# CH32F203CBT6-R1.net
KiCad netlist of a schematic drawn in Altium Designer
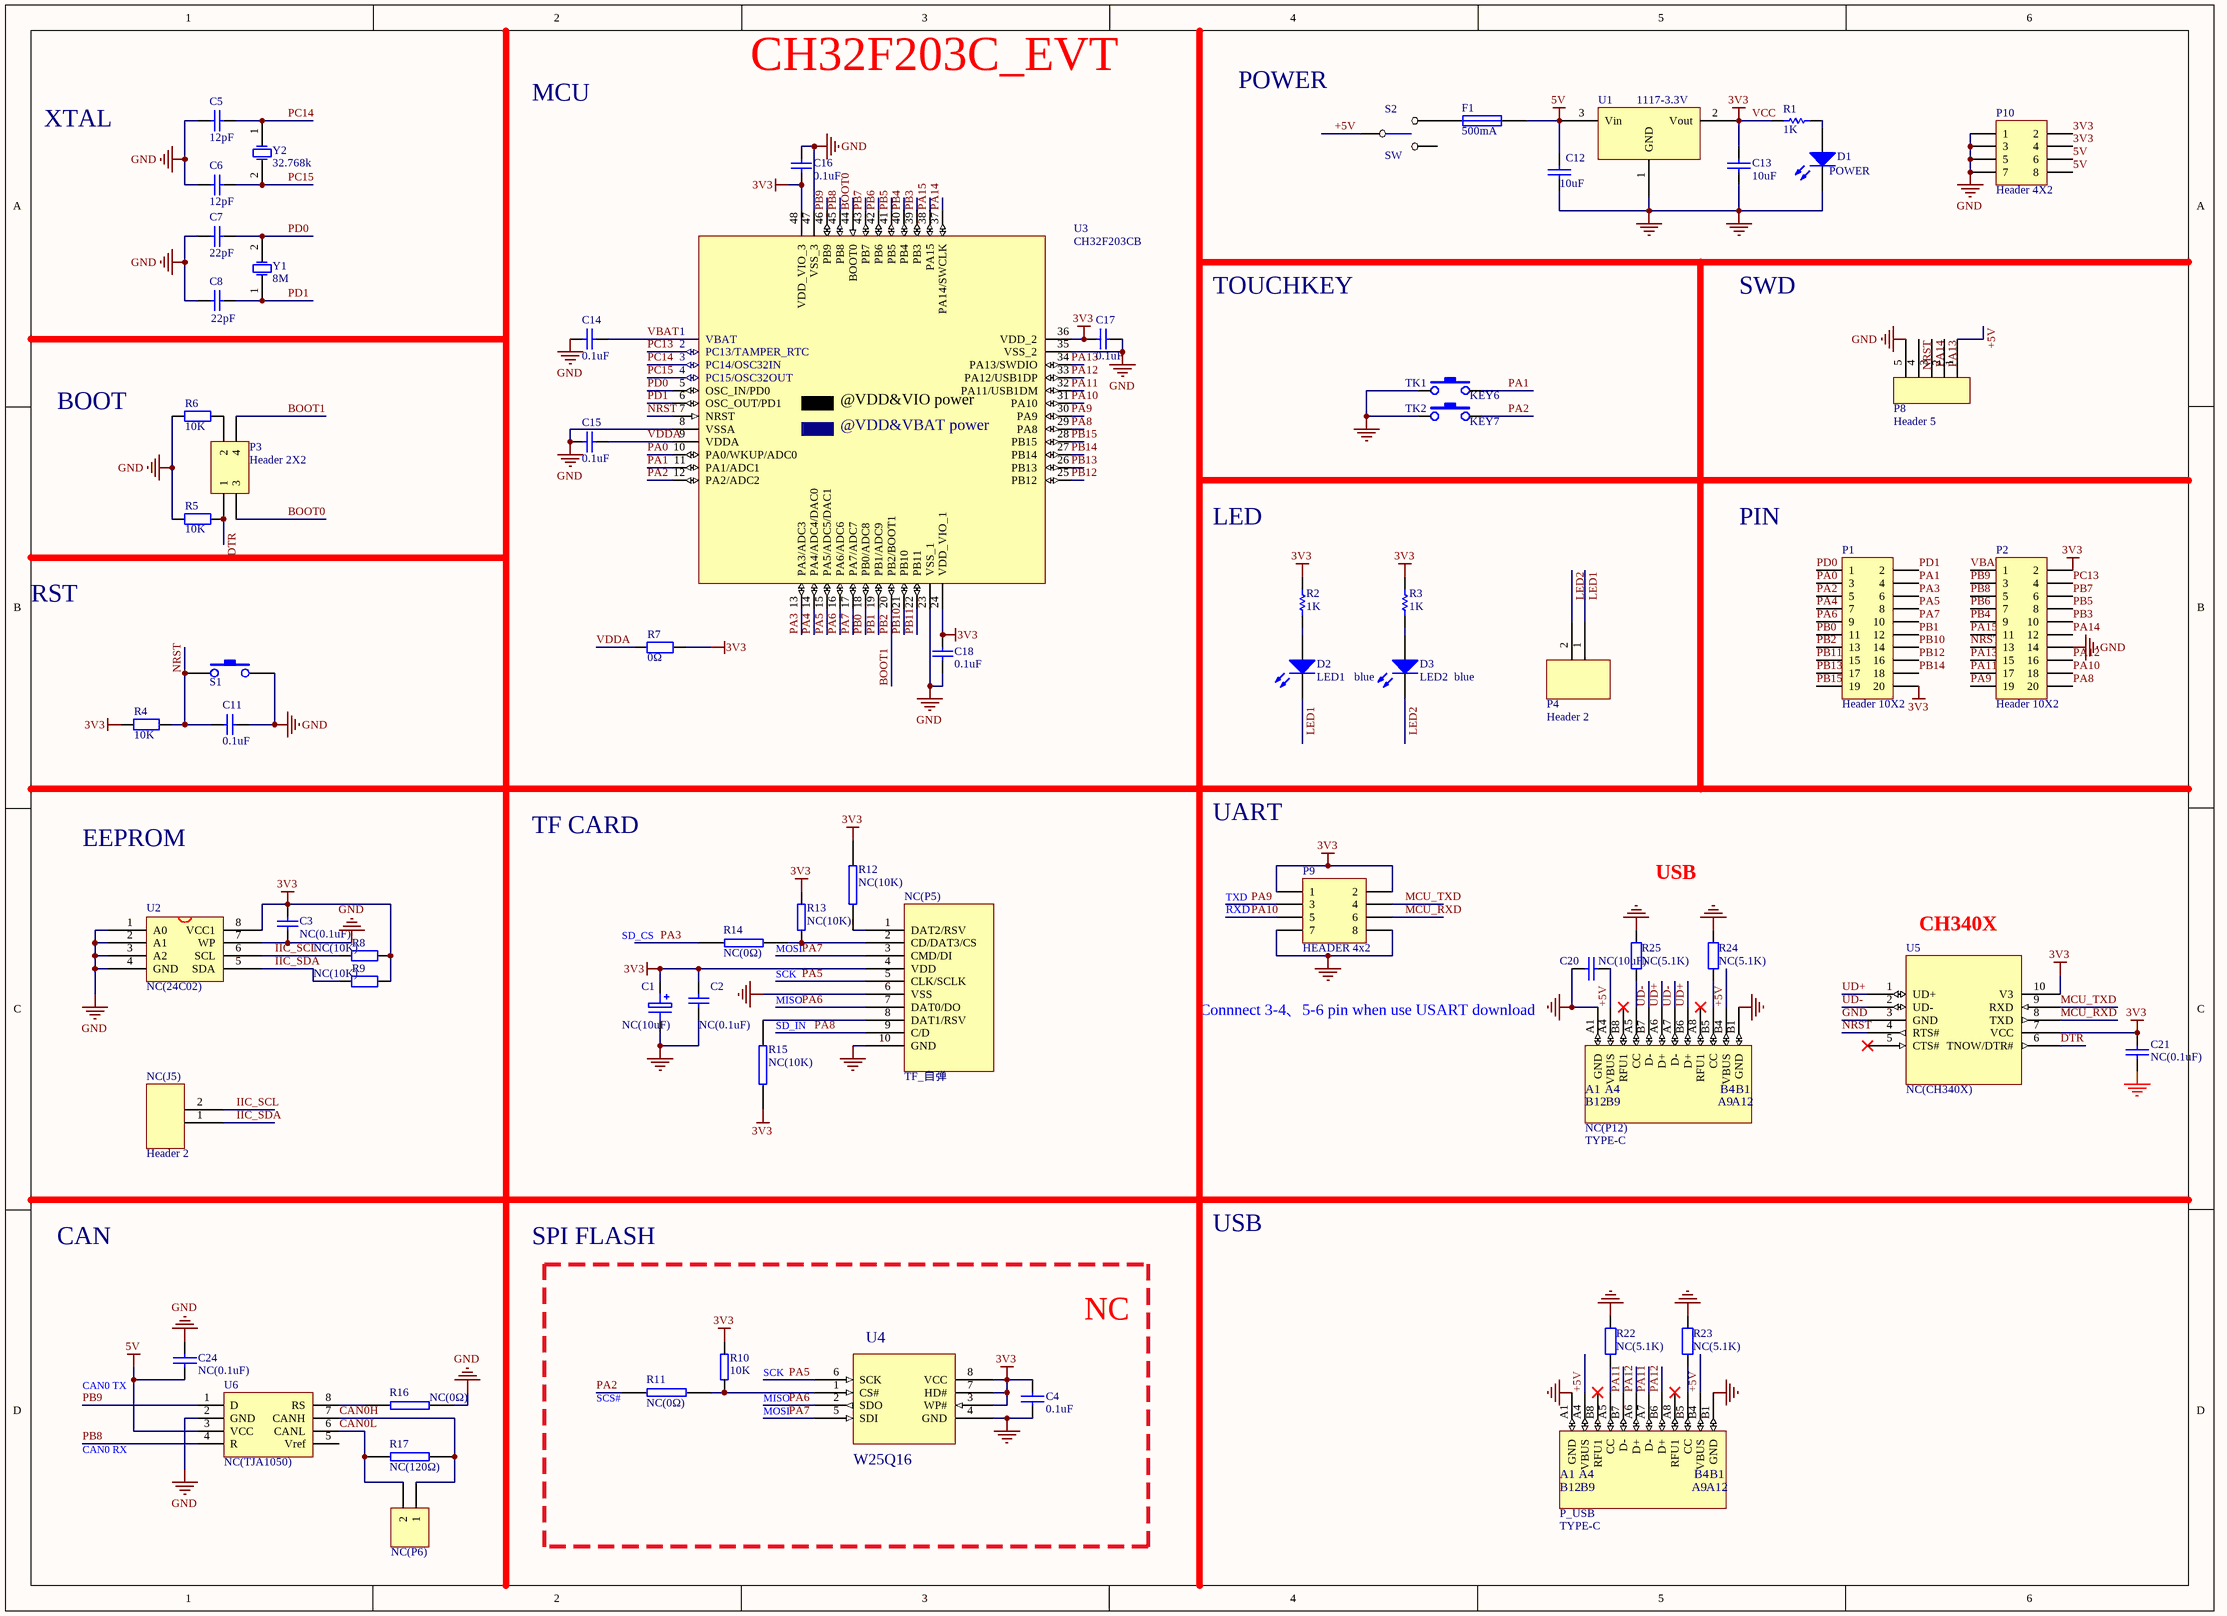
[diagram p0: CH32F203CBT6-R1.SchDoc]

(export (version "E")
  (design (tool "Eeschema 10.0.6"))
  (components
    (comp (ref "C1")
      (value "NC(10uF)")
      (footprint "3216")
      (description "Electrolytic Capacitor")
      (libsource (lib "*") (part "ELECTRO1"))
    )
    (comp (ref "C2")
      (value "NC(0.1uF)")
      (footprint "0603")
      (description "Capacitor")
      (fields (field (name "Comment") "0.1uF") (field (name "PUBLISHER") "Altium Limited"))
      (libsource (lib "*") (part "Cap"))
    )
    (comp (ref "C3")
      (value "NC(0.1uF)")
      (footprint "0603")
      (description "Capacitor")
      (fields (field (name "PUBLISHER") "Altium Limited"))
      (libsource (lib "Miscellaneous Devices") (part "Cap"))
    )
    (comp (ref "C4")
      (value "0.1uF")
      (footprint "0603")
      (description "Capacitor")
      (libsource (lib "") (part "CAP_1"))
    )
    (comp (ref "C5")
      (value "12pF")
      (footprint "0603")
      (description "Capacitor")
      (fields (field (name "PUBLISHER") "Altium Limited"))
      (libsource (lib "Miscellaneous Devices") (part "Cap"))
    )
    (comp (ref "C6")
      (value "12pF")
      (footprint "0603")
      (description "Capacitor")
      (fields (field (name "PUBLISHER") "Altium Limited"))
      (libsource (lib "Miscellaneous Devices") (part "Cap"))
    )
    (comp (ref "C7")
      (value "22pF")
      (footprint "0603")
      (description "Capacitor")
      (fields (field (name "PUBLISHER") "Altium Limited"))
      (libsource (lib "Miscellaneous Devices") (part "Cap"))
    )
    (comp (ref "C8")
      (value "22pF")
      (footprint "0603")
      (description "Capacitor")
      (fields (field (name "PUBLISHER") "Altium Limited"))
      (libsource (lib "Miscellaneous Devices") (part "Cap"))
    )
    (comp (ref "C11")
      (value "0.1uF")
      (footprint "0603")
      (description "Capacitor")
      (fields (field (name "PUBLISHER") "Altium Limited"))
      (libsource (lib "Miscellaneous Devices") (part "Cap"))
    )
    (comp (ref "C12")
      (value "10uF")
      (footprint "3216")
      (description "Capacitor")
      (libsource (lib "*") (part "CAP"))
    )
    (comp (ref "C13")
      (value "10uF")
      (footprint "0603")
      (description "Capacitor")
      (libsource (lib "*") (part "CAP"))
    )
    (comp (ref "C14")
      (value "0.1uF")
      (footprint "0603")
      (description "Capacitor")
      (fields (field (name "PUBLISHER") "Altium Limited"))
      (libsource (lib "Miscellaneous Devices") (part "Cap"))
    )
    (comp (ref "C15")
      (value "0.1uF")
      (footprint "0603")
      (description "Capacitor")
      (fields (field (name "PUBLISHER") "Altium Limited"))
      (libsource (lib "Miscellaneous Devices") (part "Cap"))
    )
    (comp (ref "C16")
      (value "0.1uF")
      (footprint "0603")
      (description "Capacitor")
      (fields (field (name "PUBLISHER") "Altium Limited"))
      (libsource (lib "Miscellaneous Devices") (part "Cap"))
    )
    (comp (ref "C17")
      (value "0.1uF")
      (footprint "0603")
      (description "Capacitor")
      (fields (field (name "PUBLISHER") "Altium Limited"))
      (libsource (lib "Miscellaneous Devices") (part "Cap"))
    )
    (comp (ref "C18")
      (value "0.1uF")
      (footprint "0603")
      (description "Capacitor")
      (fields (field (name "PUBLISHER") "Altium Limited"))
      (libsource (lib "Miscellaneous Devices") (part "Cap"))
    )
    (comp (ref "C20")
      (value "NC(10uF)")
      (footprint "3216_C")
      (description "Capacitor")
      (libsource (lib "*") (part "CAP"))
    )
    (comp (ref "C21")
      (value "NC(0.1uF)")
      (footprint "0603_C")
      (description "Capacitor")
      (libsource (lib "*") (part "CAP"))
    )
    (comp (ref "C24")
      (value "NC(0.1uF)")
      (footprint "0603")
      (description "Capacitor")
      (libsource (lib "") (part "CAP_1"))
    )
    (comp (ref "D1")
      (value "POWER")
      (footprint "0603L")
      (description "Typical INFRARED GaAs LED")
      (fields (field (name "PUBLISHER") "Altium Limited"))
      (libsource (lib "Miscellaneous Devices") (part "LED0"))
    )
    (comp (ref "D2")
      (value "LED1   blue")
      (footprint "0603L")
      (description "Typical INFRARED GaAs LED")
      (fields (field (name "PUBLISHER") "Altium Limited"))
      (libsource (lib "Miscellaneous Devices") (part "LED0"))
    )
    (comp (ref "D3")
      (value "LED2  blue")
      (footprint "0603L")
      (description "Typical INFRARED GaAs LED")
      (fields (field (name "PUBLISHER") "Altium Limited"))
      (libsource (lib "Miscellaneous Devices") (part "LED0"))
    )
    (comp (ref "F1")
      (value "500mA")
      (footprint "0603")
      (description "Fuse")
      (libsource (lib "*") (part "FUSE1"))
    )
    (comp (ref "NC(J5)")
      (value "Header 2")
      (footprint "SIP2 - 40mil")
      (libsource (lib "MYSCH") (part "2HEAD"))
    )
    (comp (ref "NC(P5)") (value "TF_自弹") (footprint "TF_CARD") (libsource (lib "*") (part "TF_自弹")))
    (comp (ref "NC(P6)")
      (value "Header 2")
      (footprint "PORT2 4.5MM")
      (description "Header, 2-Pin")
      (fields (field (name "PUBLISHER") "Altium Limited"))
      (libsource (lib "Miscellaneous Connectors") (part "Header 2"))
    )
    (comp (ref "NC(P12)")
      (value "TYPE-C")
      (footprint "TYPE-C-Receptacle-2.0")
      (libsource (lib "*") (part "TYPE-C1"))
    )
    (comp (ref "P1")
      (value "Header 10X2")
      (footprint "IDC20")
      (description "Header, 10-Pin, Dual row")
      (fields (field (name "PUBLISHER") "Altium Limited"))
      (libsource (lib "Miscellaneous Connectors") (part "Header 10X2"))
    )
    (comp (ref "P2")
      (value "Header 10X2")
      (footprint "IDC20")
      (description "Header, 10-Pin, Dual row")
      (fields (field (name "PUBLISHER") "Altium Limited"))
      (libsource (lib "Miscellaneous Connectors") (part "Header 10X2"))
    )
    (comp (ref "P3")
      (value "Header 2X2")
      (footprint "HDR2X2")
      (description "Header, 2-Pin, Dual row")
      (fields (field (name "PUBLISHER") "Altium Limited"))
      (libsource (lib "Miscellaneous Connectors") (part "Header 2X2"))
    )
    (comp (ref "P4") (value "Header 2") (footprint "SIP2 - 40mil") (libsource (lib "") (part "2HEAD_1")))
    (comp (ref "P8")
      (value "Header 5")
      (footprint "SIP5 - 40mil")
      (libsource (lib "PCB_Project1") (part "2HEAD"))
    )
    (comp (ref "P9")
      (value "HEADER 4x2")
      (footprint "MYPCB:IDC8-2.54mm")
      (description "Header, 4-Pin, Dual row")
      (libsource (lib "wch_sch_others") (part "HEADER 4x2"))
    )
    (comp (ref "P10")
      (value "Header 4X2")
      (footprint "IDC8")
      (description "Header, 4-Pin, Dual row")
      (fields (field (name "PUBLISHER") "Altium Limited"))
      (libsource (lib "Miscellaneous Connectors") (part "Header 4X2"))
    )
    (comp (ref "P_USB")
      (value "TYPE-C")
      (footprint "TYPE-C-Receptacle-2.0")
      (libsource (lib "*") (part "TYPE-C1"))
    )
    (comp (ref "R1")
      (value "1K")
      (footprint "0603")
      (description "Semiconductor Resistor")
      (fields (field (name "PUBLISHER") "Altium Limited"))
      (libsource (lib "Miscellaneous Devices") (part "Res Semi"))
    )
    (comp (ref "R2")
      (value "1K")
      (footprint "0603")
      (description "Semiconductor Resistor")
      (fields (field (name "PUBLISHER") "Altium Limited"))
      (libsource (lib "Miscellaneous Devices") (part "Res Semi"))
    )
    (comp (ref "R3")
      (value "1K")
      (footprint "0603")
      (description "Semiconductor Resistor")
      (fields (field (name "PUBLISHER") "Altium Limited"))
      (libsource (lib "Miscellaneous Devices") (part "Res Semi"))
    )
    (comp (ref "R4")
      (value "10K")
      (footprint "0603")
      (description "Resistor")
      (fields (field (name "PUBLISHER") "Altium Limited"))
      (libsource (lib "") (part "Res2_1"))
    )
    (comp (ref "R5")
      (value "10K")
      (footprint "0603")
      (description "Resistor")
      (fields (field (name "PUBLISHER") "Altium Limited"))
      (libsource (lib "") (part "Res2_1"))
    )
    (comp (ref "R6")
      (value "10K")
      (footprint "0603")
      (description "Resistor")
      (fields (field (name "PUBLISHER") "Altium Limited"))
      (libsource (lib "") (part "Res2_1"))
    )
    (comp (ref "R7")
      (value "0Ω")
      (footprint "0603")
      (description "Resistor")
      (fields (field (name "PUBLISHER") "Altium Limited"))
      (libsource (lib "") (part "Res2_1"))
    )
    (comp (ref "R8")
      (value "NC(10K)")
      (footprint "0603")
      (description "Resistor")
      (fields (field (name "PUBLISHER") "Altium Limited"))
      (libsource (lib "") (part "Res2_1"))
    )
    (comp (ref "R9")
      (value "NC(10K)")
      (footprint "0603")
      (description "Resistor")
      (fields (field (name "PUBLISHER") "Altium Limited"))
      (libsource (lib "") (part "Res2_1"))
    )
    (comp (ref "R10") (value "10K") (footprint "0603") (libsource (lib "*") (part "DZ")))
    (comp (ref "R11") (value "NC(0Ω)") (footprint "0603") (libsource (lib "*") (part "RES2")))
    (comp (ref "R12") (value "NC(10K)") (footprint "0603") (libsource (lib "*") (part "RES2")))
    (comp (ref "R13") (value "NC(10K)") (footprint "0603") (libsource (lib "*") (part "DZ")))
    (comp (ref "R14") (value "NC(0Ω)") (footprint "0603") (libsource (lib "*") (part "RES2")))
    (comp (ref "R15") (value "NC(10K)") (footprint "0603") (libsource (lib "*") (part "RES2")))
    (comp (ref "R16") (value "NC(0Ω)") (footprint "0603") (libsource (lib "*") (part "RES2")))
    (comp (ref "R17") (value "NC(120Ω)") (footprint "0603") (libsource (lib "*") (part "RES2")))
    (comp (ref "R22")
      (value "NC(5.1K)")
      (footprint "0603")
      (description "Resistor")
      (libsource (lib "Miscellaneous Devices") (part "Res2"))
    )
    (comp (ref "R23")
      (value "NC(5.1K)")
      (footprint "0603")
      (description "Resistor")
      (libsource (lib "Miscellaneous Devices") (part "Res2"))
    )
    (comp (ref "R24")
      (value "NC(5.1K)")
      (footprint "0603")
      (description "Resistor")
      (libsource (lib "Miscellaneous Devices") (part "Res2"))
    )
    (comp (ref "R25")
      (value "NC(5.1K)")
      (footprint "0603")
      (description "Resistor")
      (libsource (lib "Miscellaneous Devices") (part "Res2"))
    )
    (comp (ref "S1") (value "KEY") (footprint "贴片按键") (libsource (lib "CCDXPLIB") (part "KEY")))
    (comp (ref "S2") (value "SW") (footprint "KEY2") (libsource (lib "MYSCH") (part "SW")))
    (comp (ref "TK1") (value "KEY6") (footprint "KEY68") (libsource (lib "*") (part "KEY")))
    (comp (ref "TK2") (value "KEY7") (footprint "KEY68") (libsource (lib "*") (part "KEY")))
    (comp (ref "U1")
      (value "1117-3.3V")
      (footprint "SOT-223")
      (libsource (lib "wch_sch_others") (part "1117-3.3V"))
    )
    (comp (ref "U2") (value "NC(24C02)") (footprint "SOP8") (libsource (lib "Elite_SCH") (part "24C256")))
    (comp (ref "U3")
      (value "CH32F203CB")
      (footprint "LQFP48")
      (description "ARM M3 HD-MCU, 144MHz, 8*UART, 10*Timer, 4*OPA")
      (libsource (lib "CHXXX") (part "CH32F203CB"))
    )
    (comp (ref "U4")
      (value "W25Q16")
      (footprint "016 SO-8")
      (libsource (lib "*") (part "Pro89C.tmp_25F512_2"))
    )
    (comp (ref "U5")
      (value "NC(CH340X)")
      (footprint "MSOP10")
      (description "USB to TTL Serial / UART")
      (libsource (lib "CHXXX") (part "CH340X"))
    )
    (comp (ref "U6") (value "NC(TJA1050)") (footprint "SOP8") (libsource (lib "CAN") (part "Component_1")))
    (comp (ref "Y1")
      (value "8M")
      (footprint "XT62/28")
      (description "Crystal Oscillator")
      (fields (field (name "PUBLISHER") "Altium Limited"))
      (libsource (lib "Miscellaneous Devices") (part "XTAL"))
    )
    (comp (ref "Y2")
      (value "32.768k")
      (footprint "FC-135")
      (description "Crystal Oscillator")
      (fields (field (name "PUBLISHER") "Altium Limited"))
      (libsource (lib "Miscellaneous Devices") (part "XTAL"))
    )
  )
  (nets
    (net (code "1") (name "/+5V") (class "Default")
      (node (ref "C20") (pin "2") (pinfunction "2_2") (pintype "passive"))
      (node (ref "NC(P12)") (pin "A4") (pinfunction "VBUS_A4") (pintype "bidirectional"))
      (node (ref "NC(P12)") (pin "B4") (pinfunction "VBUS_B4") (pintype "bidirectional"))
      (node (ref "P8") (pin "1") (pintype "passive"))
      (node (ref "P_USB") (pin "A4") (pinfunction "VBUS_A4") (pintype "bidirectional"))
      (node (ref "P_USB") (pin "B4") (pinfunction "VBUS_B4") (pintype "bidirectional"))
      (node (ref "S2") (pin "1") (pinfunction "1_1") (pintype "passive"))
    )
    (net (code "3") (name "/BOOT0") (class "Default")
      (node (ref "P3") (pin "3") (pinfunction "3_3") (pintype "passive"))
      (node (ref "U3") (pin "44") (pinfunction "BOOT0_44") (pintype "input"))
    )
    (net (code "4") (name "/BOOT1") (class "Default")
      (node (ref "P1") (pin "13") (pinfunction "13_13") (pintype "passive"))
      (node (ref "P3") (pin "4") (pinfunction "4_4") (pintype "passive"))
      (node (ref "U3") (pin "20") (pinfunction "PB2/BOOT1_20") (pintype "bidirectional"))
    )
    (net (code "5") (name "/CAN0H") (class "Default")
      (node (ref "NC(P6)") (pin "1") (pinfunction "1_1") (pintype "passive"))
      (node (ref "R17") (pin "1") (pinfunction "1_1") (pintype "passive"))
      (node (ref "U6") (pin "7") (pinfunction "CANH_7") (pintype "passive"))
    )
    (net (code "6") (name "/CAN0L") (class "Default")
      (node (ref "NC(P6)") (pin "2") (pinfunction "2_2") (pintype "passive"))
      (node (ref "R17") (pin "2") (pinfunction "2_2") (pintype "passive"))
      (node (ref "U6") (pin "6") (pinfunction "CANL_6") (pintype "passive"))
    )
    (net (code "7") (name "/DTR") (class "Default")
      (node (ref "P3") (pin "1") (pinfunction "1_1") (pintype "passive"))
      (node (ref "R5") (pin "1") (pinfunction "1_1") (pintype "passive"))
      (node (ref "U5") (pin "6") (pinfunction "TNOW/DTR#_6") (pintype "output"))
    )
    (net (code "8") (name "/IIC_SCL") (class "Default")
      (node (ref "NC(J5)") (pin "2") (pintype "passive"))
      (node (ref "R8") (pin "2") (pinfunction "2_2") (pintype "passive"))
      (node (ref "U2") (pin "6") (pinfunction "SCL_6") (pintype "passive"))
    )
    (net (code "9") (name "/IIC_SDA") (class "Default")
      (node (ref "NC(J5)") (pin "1") (pintype "passive"))
      (node (ref "R9") (pin "2") (pinfunction "2_2") (pintype "passive"))
      (node (ref "U2") (pin "5") (pinfunction "SDA_5") (pintype "passive"))
    )
    (net (code "10") (name "/LED1") (class "Default")
      (node (ref "D2") (pin "2") (pinfunction "K_2") (pintype "passive"))
      (node (ref "P4") (pin "1") (pintype "passive"))
    )
    (net (code "11") (name "/LED2") (class "Default")
      (node (ref "D3") (pin "2") (pinfunction "K_2") (pintype "passive"))
      (node (ref "P4") (pin "2") (pintype "passive"))
    )
    (net (code "12") (name "/MCU_RXD") (class "Default")
      (node (ref "P9") (pin "6") (pinfunction "6_6") (pintype "passive"))
      (node (ref "U5") (pin "8") (pinfunction "TXD_8") (pintype "output"))
    )
    (net (code "13") (name "/MCU_TXD") (class "Default")
      (node (ref "P9") (pin "4") (pinfunction "4_4") (pintype "passive"))
      (node (ref "U5") (pin "9") (pinfunction "RXD_9") (pintype "input"))
    )
    (net (code "14") (name "/NRST") (class "Default")
      (node (ref "C11") (pin "2") (pinfunction "2_2") (pintype "passive"))
      (node (ref "P2") (pin "13") (pinfunction "13_13") (pintype "passive"))
      (node (ref "P8") (pin "4") (pintype "passive"))
      (node (ref "R4") (pin "1") (pinfunction "1_1") (pintype "passive"))
      (node (ref "S1") (pin "1") (pinfunction "1_1") (pintype "passive"))
      (node (ref "U3") (pin "7") (pinfunction "NRST_7") (pintype "input"))
      (node (ref "U5") (pin "4") (pinfunction "RTS#_4") (pintype "output"))
    )
    (net (code "15") (name "/PA0") (class "Default")
      (node (ref "P1") (pin "3") (pinfunction "3_3") (pintype "passive"))
      (node (ref "U3") (pin "10") (pinfunction "PA0/WKUP/ADC0_10") (pintype "bidirectional"))
    )
    (net (code "16") (name "/PA1") (class "Default")
      (node (ref "P1") (pin "4") (pinfunction "4_4") (pintype "passive"))
      (node (ref "TK1") (pin "1") (pintype "passive"))
      (node (ref "U3") (pin "11") (pinfunction "PA1/ADC1_11") (pintype "bidirectional"))
    )
    (net (code "17") (name "/PA2") (class "Default")
      (node (ref "P1") (pin "5") (pinfunction "5_5") (pintype "passive"))
      (node (ref "R11") (pin "2") (pinfunction "2_2") (pintype "passive"))
      (node (ref "TK2") (pin "1") (pintype "passive"))
      (node (ref "U3") (pin "12") (pinfunction "PA2/ADC2_12") (pintype "bidirectional"))
    )
    (net (code "18") (name "/PA3") (class "Default")
      (node (ref "P1") (pin "6") (pinfunction "6_6") (pintype "passive"))
      (node (ref "R14") (pin "2") (pinfunction "2_2") (pintype "passive"))
      (node (ref "U3") (pin "13") (pinfunction "PA3/ADC3_13") (pintype "bidirectional"))
    )
    (net (code "19") (name "/PA4") (class "Default")
      (node (ref "P1") (pin "7") (pinfunction "7_7") (pintype "passive"))
      (node (ref "U3") (pin "14") (pinfunction "PA4/ADC4/DAC0_14") (pintype "bidirectional"))
    )
    (net (code "20") (name "/PA5") (class "Default")
      (node (ref "NC(P5)") (pin "5") (pinfunction "CLK/SCLK_5") (pintype "passive"))
      (node (ref "P1") (pin "8") (pinfunction "8_8") (pintype "passive"))
      (node (ref "U3") (pin "15") (pinfunction "PA5/ADC5/DAC1_15") (pintype "bidirectional"))
      (node (ref "U4") (pin "6") (pinfunction "SCK_6") (pintype "input"))
    )
    (net (code "21") (name "/PA6") (class "Default")
      (node (ref "NC(P5)") (pin "7") (pinfunction "DAT0/DO_7") (pintype "passive"))
      (node (ref "P1") (pin "9") (pinfunction "9_9") (pintype "passive"))
      (node (ref "U3") (pin "16") (pinfunction "PA6/ADC6_16") (pintype "bidirectional"))
      (node (ref "U4") (pin "2") (pinfunction "SDO_2") (pintype "output"))
    )
    (net (code "22") (name "/PA7") (class "Default")
      (node (ref "NC(P5)") (pin "3") (pinfunction "CMD/DI_3") (pintype "passive"))
      (node (ref "P1") (pin "10") (pinfunction "10_10") (pintype "passive"))
      (node (ref "U3") (pin "17") (pinfunction "PA7/ADC7_17") (pintype "bidirectional"))
      (node (ref "U4") (pin "5") (pinfunction "SDI_5") (pintype "input"))
    )
    (net (code "23") (name "/PA8") (class "Default")
      (node (ref "NC(P5)") (pin "9") (pinfunction "C/D_9") (pintype "passive"))
      (node (ref "P2") (pin "20") (pinfunction "20_20") (pintype "passive"))
      (node (ref "U3") (pin "29") (pinfunction "PA8_29") (pintype "bidirectional"))
    )
    (net (code "24") (name "/PA9") (class "Default")
      (node (ref "P2") (pin "19") (pinfunction "19_19") (pintype "passive"))
      (node (ref "P9") (pin "3") (pinfunction "3_3") (pintype "passive"))
      (node (ref "U3") (pin "30") (pinfunction "PA9_30") (pintype "bidirectional"))
    )
    (net (code "25") (name "/PA10") (class "Default")
      (node (ref "P2") (pin "18") (pinfunction "18_18") (pintype "passive"))
      (node (ref "P9") (pin "5") (pinfunction "5_5") (pintype "passive"))
      (node (ref "U3") (pin "31") (pinfunction "PA10_31") (pintype "bidirectional"))
    )
    (net (code "26") (name "/PA11") (class "Default")
      (node (ref "P2") (pin "17") (pinfunction "17_17") (pintype "passive"))
      (node (ref "P_USB") (pin "A7") (pinfunction "D-_A7") (pintype "bidirectional"))
      (node (ref "P_USB") (pin "B7") (pinfunction "D-_B7") (pintype "bidirectional"))
      (node (ref "U3") (pin "32") (pinfunction "PA11/USB1DM_32") (pintype "bidirectional"))
    )
    (net (code "27") (name "/PA12") (class "Default")
      (node (ref "P2") (pin "16") (pinfunction "16_16") (pintype "passive"))
      (node (ref "P_USB") (pin "A6") (pinfunction "D+_A6") (pintype "bidirectional"))
      (node (ref "P_USB") (pin "B6") (pinfunction "D+_B6") (pintype "bidirectional"))
      (node (ref "U3") (pin "33") (pinfunction "PA12/USB1DP_33") (pintype "bidirectional"))
    )
    (net (code "28") (name "/PA13") (class "Default")
      (node (ref "P2") (pin "15") (pinfunction "15_15") (pintype "passive"))
      (node (ref "P8") (pin "2") (pintype "passive"))
      (node (ref "U3") (pin "34") (pinfunction "PA13/SWDIO_34") (pintype "bidirectional"))
    )
    (net (code "29") (name "/PA14") (class "Default")
      (node (ref "P2") (pin "12") (pinfunction "12_12") (pintype "passive"))
      (node (ref "P8") (pin "3") (pintype "passive"))
      (node (ref "U3") (pin "37") (pinfunction "PA14/SWCLK_37") (pintype "bidirectional"))
    )
    (net (code "30") (name "/PA15") (class "Default")
      (node (ref "P2") (pin "11") (pinfunction "11_11") (pintype "passive"))
      (node (ref "U3") (pin "38") (pinfunction "PA15_38") (pintype "bidirectional"))
    )
    (net (code "31") (name "/PB0") (class "Default")
      (node (ref "P1") (pin "11") (pinfunction "11_11") (pintype "passive"))
      (node (ref "U3") (pin "18") (pinfunction "PB0/ADC8_18") (pintype "bidirectional"))
    )
    (net (code "32") (name "/PB1") (class "Default")
      (node (ref "P1") (pin "12") (pinfunction "12_12") (pintype "passive"))
      (node (ref "U3") (pin "19") (pinfunction "PB1/ADC9_19") (pintype "bidirectional"))
    )
    (net (code "33") (name "/PB3") (class "Default")
      (node (ref "P2") (pin "10") (pinfunction "10_10") (pintype "passive"))
      (node (ref "U3") (pin "39") (pinfunction "PB3_39") (pintype "bidirectional"))
    )
    (net (code "34") (name "/PB4") (class "Default")
      (node (ref "P2") (pin "9") (pinfunction "9_9") (pintype "passive"))
      (node (ref "U3") (pin "40") (pinfunction "PB4_40") (pintype "bidirectional"))
    )
    (net (code "35") (name "/PB5") (class "Default")
      (node (ref "P2") (pin "8") (pinfunction "8_8") (pintype "passive"))
      (node (ref "U3") (pin "41") (pinfunction "PB5_41") (pintype "bidirectional"))
    )
    (net (code "36") (name "/PB6") (class "Default")
      (node (ref "P2") (pin "7") (pinfunction "7_7") (pintype "passive"))
      (node (ref "U3") (pin "42") (pinfunction "PB6_42") (pintype "bidirectional"))
    )
    (net (code "37") (name "/PB7") (class "Default")
      (node (ref "P2") (pin "6") (pinfunction "6_6") (pintype "passive"))
      (node (ref "U3") (pin "43") (pinfunction "PB7_43") (pintype "bidirectional"))
    )
    (net (code "38") (name "/PB8") (class "Default")
      (node (ref "P2") (pin "5") (pinfunction "5_5") (pintype "passive"))
      (node (ref "U3") (pin "45") (pinfunction "PB8_45") (pintype "bidirectional"))
      (node (ref "U6") (pin "4") (pinfunction "R_4") (pintype "passive"))
    )
    (net (code "39") (name "/PB9") (class "Default")
      (node (ref "P2") (pin "3") (pinfunction "3_3") (pintype "passive"))
      (node (ref "U3") (pin "46") (pinfunction "PB9_46") (pintype "bidirectional"))
      (node (ref "U6") (pin "1") (pinfunction "D_1") (pintype "passive"))
    )
    (net (code "40") (name "/PB10") (class "Default")
      (node (ref "P1") (pin "14") (pinfunction "14_14") (pintype "passive"))
      (node (ref "U3") (pin "21") (pinfunction "PB10_21") (pintype "bidirectional"))
    )
    (net (code "41") (name "/PB11") (class "Default")
      (node (ref "P1") (pin "15") (pinfunction "15_15") (pintype "passive"))
      (node (ref "U3") (pin "22") (pinfunction "PB11_22") (pintype "bidirectional"))
    )
    (net (code "42") (name "/PB12") (class "Default")
      (node (ref "P1") (pin "16") (pinfunction "16_16") (pintype "passive"))
      (node (ref "U3") (pin "25") (pinfunction "PB12_25") (pintype "bidirectional"))
    )
    (net (code "43") (name "/PB13") (class "Default")
      (node (ref "P1") (pin "17") (pinfunction "17_17") (pintype "passive"))
      (node (ref "U3") (pin "26") (pinfunction "PB13_26") (pintype "bidirectional"))
    )
    (net (code "44") (name "/PB14") (class "Default")
      (node (ref "P1") (pin "18") (pinfunction "18_18") (pintype "passive"))
      (node (ref "U3") (pin "27") (pinfunction "PB14_27") (pintype "bidirectional"))
    )
    (net (code "45") (name "/PB15") (class "Default")
      (node (ref "P1") (pin "19") (pinfunction "19_19") (pintype "passive"))
      (node (ref "U3") (pin "28") (pinfunction "PB15_28") (pintype "bidirectional"))
    )
    (net (code "46") (name "/PC13") (class "Default")
      (node (ref "P2") (pin "4") (pinfunction "4_4") (pintype "passive"))
      (node (ref "U3") (pin "2") (pinfunction "PC13/TAMPER_RTC_2") (pintype "bidirectional"))
    )
    (net (code "47") (name "/PC14") (class "Default")
      (node (ref "C5") (pin "1") (pinfunction "1_1") (pintype "passive"))
      (node (ref "U3") (pin "3") (pinfunction "PC14/OSC32IN_3") (pintype "bidirectional"))
      (node (ref "Y2") (pin "1") (pinfunction "OSC1_1") (pintype "passive"))
    )
    (net (code "48") (name "/PC15") (class "Default")
      (node (ref "C6") (pin "1") (pinfunction "1_1") (pintype "passive"))
      (node (ref "U3") (pin "4") (pinfunction "PC15/OSC32OUT_4") (pintype "bidirectional"))
      (node (ref "Y2") (pin "2") (pinfunction "OSC2_2") (pintype "passive"))
    )
    (net (code "49") (name "/PD0") (class "Default")
      (node (ref "C7") (pin "2") (pinfunction "2_2") (pintype "passive"))
      (node (ref "P1") (pin "1") (pinfunction "1_1") (pintype "passive"))
      (node (ref "U3") (pin "5") (pinfunction "OSC_IN/PD0_5") (pintype "bidirectional"))
      (node (ref "Y1") (pin "2") (pinfunction "OSC2_2") (pintype "passive"))
    )
    (net (code "50") (name "/PD1") (class "Default")
      (node (ref "C8") (pin "2") (pinfunction "2_2") (pintype "passive"))
      (node (ref "P1") (pin "2") (pinfunction "2_2") (pintype "passive"))
      (node (ref "U3") (pin "6") (pinfunction "OSC_OUT/PD1_6") (pintype "bidirectional"))
      (node (ref "Y1") (pin "1") (pinfunction "OSC1_1") (pintype "passive"))
    )
    (net (code "51") (name "/UD+") (class "Default")
      (node (ref "NC(P12)") (pin "A6") (pinfunction "D+_A6") (pintype "bidirectional"))
      (node (ref "NC(P12)") (pin "B6") (pinfunction "D+_B6") (pintype "bidirectional"))
      (node (ref "U5") (pin "1") (pinfunction "UD+_1") (pintype "bidirectional"))
    )
    (net (code "52") (name "/UD-") (class "Default")
      (node (ref "NC(P12)") (pin "A7") (pinfunction "D-_A7") (pintype "bidirectional"))
      (node (ref "NC(P12)") (pin "B7") (pinfunction "D-_B7") (pintype "bidirectional"))
      (node (ref "U5") (pin "2") (pinfunction "UD-_2") (pintype "bidirectional"))
    )
    (net (code "53") (name "/VBAT") (class "Default")
      (node (ref "C14") (pin "1") (pinfunction "1_1") (pintype "passive"))
      (node (ref "P2") (pin "1") (pinfunction "1_1") (pintype "passive"))
      (node (ref "U3") (pin "1") (pinfunction "VBAT_1") (pintype "power_in"))
    )
    (net (code "54") (name "/VDDA") (class "Default")
      (node (ref "C15") (pin "1") (pinfunction "1_1") (pintype "passive"))
      (node (ref "R7") (pin "2") (pinfunction "2_2") (pintype "passive"))
      (node (ref "U3") (pin "9") (pinfunction "VDDA_9") (pintype "power_in"))
    )
    (net (code "55") (name "3V3") (class "Default")
      (node (ref "C1") (pin "1") (pinfunction "1_1") (pintype "passive"))
      (node (ref "C13") (pin "1") (pinfunction "1_1") (pintype "passive"))
      (node (ref "C16") (pin "2") (pinfunction "2_2") (pintype "passive"))
      (node (ref "C17") (pin "2") (pinfunction "2_2") (pintype "passive"))
      (node (ref "C18") (pin "2") (pinfunction "2_2") (pintype "passive"))
      (node (ref "C2") (pin "1") (pinfunction "1_1") (pintype "passive"))
      (node (ref "C21") (pin "1") (pinfunction "1_1") (pintype "passive"))
      (node (ref "C3") (pin "2") (pinfunction "2_2") (pintype "passive"))
      (node (ref "C4") (pin "2") (pinfunction "2_2") (pintype "passive"))
      (node (ref "NC(P5)") (pin "4") (pinfunction "VDD_4") (pintype "passive"))
      (node (ref "P1") (pin "20") (pinfunction "20_20") (pintype "passive"))
      (node (ref "P10") (pin "2") (pinfunction "2_2") (pintype "passive"))
      (node (ref "P10") (pin "4") (pinfunction "4_4") (pintype "passive"))
      (node (ref "P2") (pin "2") (pinfunction "2_2") (pintype "passive"))
      (node (ref "P9") (pin "1") (pinfunction "1_1") (pintype "passive"))
      (node (ref "P9") (pin "2") (pinfunction "2_2") (pintype "passive"))
      (node (ref "R1") (pin "2") (pinfunction "2_2") (pintype "passive"))
      (node (ref "R10") (pin "2") (pintype "passive"))
      (node (ref "R12") (pin "2") (pinfunction "2_2") (pintype "passive"))
      (node (ref "R13") (pin "2") (pintype "passive"))
      (node (ref "R15") (pin "1") (pinfunction "1_1") (pintype "passive"))
      (node (ref "R2") (pin "1") (pinfunction "1_1") (pintype "passive"))
      (node (ref "R3") (pin "1") (pinfunction "1_1") (pintype "passive"))
      (node (ref "R4") (pin "2") (pinfunction "2_2") (pintype "passive"))
      (node (ref "R7") (pin "1") (pinfunction "1_1") (pintype "passive"))
      (node (ref "R8") (pin "1") (pinfunction "1_1") (pintype "passive"))
      (node (ref "R9") (pin "1") (pinfunction "1_1") (pintype "passive"))
      (node (ref "U1") (pin "2") (pinfunction "Vout_2") (pintype "passive"))
      (node (ref "U2") (pin "8") (pinfunction "VCC1_8") (pintype "passive"))
      (node (ref "U3") (pin "24") (pinfunction "VDD_VIO_1_24") (pintype "power_in"))
      (node (ref "U3") (pin "36") (pinfunction "VDD_2_36") (pintype "power_in"))
      (node (ref "U3") (pin "48") (pinfunction "VDD_VIO_3_48") (pintype "power_in"))
      (node (ref "U4") (pin "3") (pinfunction "WP#_3") (pintype "input"))
      (node (ref "U4") (pin "7") (pinfunction "HD#_7") (pintype "power_in"))
      (node (ref "U4") (pin "8") (pinfunction "VCC_8") (pintype "power_in"))
      (node (ref "U5") (pin "10") (pinfunction "V3_10") (pintype "power_in"))
      (node (ref "U5") (pin "7") (pinfunction "VCC_7") (pintype "power_in"))
    )
    (net (code "56") (name "5V") (class "Default")
      (node (ref "C12") (pin "1") (pinfunction "1_1") (pintype "passive"))
      (node (ref "C24") (pin "2") (pinfunction "2_2") (pintype "passive"))
      (node (ref "F1") (pin "2") (pinfunction "2_2") (pintype "passive"))
      (node (ref "P10") (pin "6") (pinfunction "6_6") (pintype "passive"))
      (node (ref "P10") (pin "8") (pinfunction "8_8") (pintype "passive"))
      (node (ref "U1") (pin "3") (pinfunction "Vin_3") (pintype "passive"))
      (node (ref "U6") (pin "3") (pinfunction "VCC_3") (pintype "passive"))
    )
    (net (code "57") (name "GND") (class "Default")
      (node (ref "C1") (pin "2") (pinfunction "2_2") (pintype "passive"))
      (node (ref "C11") (pin "1") (pinfunction "1_1") (pintype "passive"))
      (node (ref "C12") (pin "2") (pinfunction "2_2") (pintype "passive"))
      (node (ref "C13") (pin "2") (pinfunction "2_2") (pintype "passive"))
      (node (ref "C14") (pin "2") (pinfunction "2_2") (pintype "passive"))
      (node (ref "C15") (pin "2") (pinfunction "2_2") (pintype "passive"))
      (node (ref "C16") (pin "1") (pinfunction "1_1") (pintype "passive"))
      (node (ref "C17") (pin "1") (pinfunction "1_1") (pintype "passive"))
      (node (ref "C18") (pin "1") (pinfunction "1_1") (pintype "passive"))
      (node (ref "C2") (pin "2") (pinfunction "2_2") (pintype "passive"))
      (node (ref "C20") (pin "1") (pinfunction "1_1") (pintype "passive"))
      (node (ref "C21") (pin "2") (pinfunction "2_2") (pintype "passive"))
      (node (ref "C24") (pin "1") (pinfunction "1_1") (pintype "passive"))
      (node (ref "C3") (pin "1") (pinfunction "1_1") (pintype "passive"))
      (node (ref "C4") (pin "1") (pinfunction "1_1") (pintype "passive"))
      (node (ref "C5") (pin "2") (pinfunction "2_2") (pintype "passive"))
      (node (ref "C6") (pin "2") (pinfunction "2_2") (pintype "passive"))
      (node (ref "C7") (pin "1") (pinfunction "1_1") (pintype "passive"))
      (node (ref "C8") (pin "1") (pinfunction "1_1") (pintype "passive"))
      (node (ref "D1") (pin "2") (pinfunction "K_2") (pintype "passive"))
      (node (ref "NC(P12)") (pin "A1") (pinfunction "GND_A1") (pintype "bidirectional"))
      (node (ref "NC(P12)") (pin "B1") (pinfunction "GND_B1") (pintype "bidirectional"))
      (node (ref "NC(P5)") (pin "10") (pinfunction "GND_10") (pintype "passive"))
      (node (ref "NC(P5)") (pin "6") (pinfunction "VSS_6") (pintype "passive"))
      (node (ref "P10") (pin "1") (pinfunction "1_1") (pintype "passive"))
      (node (ref "P10") (pin "3") (pinfunction "3_3") (pintype "passive"))
      (node (ref "P10") (pin "5") (pinfunction "5_5") (pintype "passive"))
      (node (ref "P10") (pin "7") (pinfunction "7_7") (pintype "passive"))
      (node (ref "P2") (pin "14") (pinfunction "14_14") (pintype "passive"))
      (node (ref "P8") (pin "5") (pintype "passive"))
      (node (ref "P9") (pin "7") (pinfunction "7_7") (pintype "passive"))
      (node (ref "P9") (pin "8") (pinfunction "8_8") (pintype "passive"))
      (node (ref "P_USB") (pin "A1") (pinfunction "GND_A1") (pintype "bidirectional"))
      (node (ref "P_USB") (pin "B1") (pinfunction "GND_B1") (pintype "bidirectional"))
      (node (ref "R16") (pin "1") (pinfunction "1_1") (pintype "passive"))
      (node (ref "R22") (pin "2") (pinfunction "2_2") (pintype "passive"))
      (node (ref "R23") (pin "2") (pinfunction "2_2") (pintype "passive"))
      (node (ref "R24") (pin "2") (pinfunction "2_2") (pintype "passive"))
      (node (ref "R25") (pin "2") (pinfunction "2_2") (pintype "passive"))
      (node (ref "R5") (pin "2") (pinfunction "2_2") (pintype "passive"))
      (node (ref "R6") (pin "2") (pinfunction "2_2") (pintype "passive"))
      (node (ref "S1") (pin "3") (pinfunction "3_3") (pintype "passive"))
      (node (ref "TK1") (pin "3") (pintype "passive"))
      (node (ref "TK2") (pin "3") (pintype "passive"))
      (node (ref "U1") (pin "1") (pinfunction "GND_1") (pintype "passive"))
      (node (ref "U2") (pin "1") (pinfunction "A0_1") (pintype "passive"))
      (node (ref "U2") (pin "2") (pinfunction "A1_2") (pintype "passive"))
      (node (ref "U2") (pin "3") (pinfunction "A2_3") (pintype "passive"))
      (node (ref "U2") (pin "4") (pinfunction "GND_4") (pintype "passive"))
      (node (ref "U2") (pin "7") (pinfunction "WP_7") (pintype "passive"))
      (node (ref "U3") (pin "23") (pinfunction "VSS_1_23") (pintype "power_in"))
      (node (ref "U3") (pin "35") (pinfunction "VSS_2_35") (pintype "power_in"))
      (node (ref "U3") (pin "47") (pinfunction "VSS_3_47") (pintype "power_in"))
      (node (ref "U3") (pin "8") (pinfunction "VSSA_8") (pintype "power_in"))
      (node (ref "U4") (pin "4") (pinfunction "GND_4") (pintype "power_in"))
      (node (ref "U5") (pin "3") (pinfunction "GND_3") (pintype "power_in"))
      (node (ref "U6") (pin "2") (pinfunction "GND_2") (pintype "passive"))
    )
    (net (code "58") (name "Net-(D1-A)") (class "Default")
      (node (ref "D1") (pin "1") (pinfunction "A_1") (pintype "passive"))
      (node (ref "R1") (pin "1") (pinfunction "1_1") (pintype "passive"))
    )
    (net (code "59") (name "Net-(D2-A)") (class "Default")
      (node (ref "D2") (pin "1") (pinfunction "A_1") (pintype "passive"))
      (node (ref "R2") (pin "2") (pinfunction "2_2") (pintype "passive"))
    )
    (net (code "60") (name "Net-(D3-A)") (class "Default")
      (node (ref "D3") (pin "1") (pinfunction "A_1") (pintype "passive"))
      (node (ref "R3") (pin "2") (pinfunction "2_2") (pintype "passive"))
    )
    (net (code "61") (name "Net-(F1-Pad1)") (class "Default")
      (node (ref "F1") (pin "1") (pinfunction "1_1") (pintype "passive"))
      (node (ref "S2") (pin "2") (pinfunction "2_2") (pintype "passive"))
    )
    (net (code "62") (name "Net-(NC(P5)-CD{slash}DAT3{slash}CS)") (class "Default")
      (node (ref "NC(P5)") (pin "2") (pinfunction "CD/DAT3/CS_2") (pintype "passive"))
      (node (ref "R13") (pin "1") (pintype "passive"))
      (node (ref "R14") (pin "1") (pinfunction "1_1") (pintype "passive"))
    )
    (net (code "63") (name "Net-(NC(P5)-DAT1{slash}RSV)") (class "Default")
      (node (ref "NC(P5)") (pin "8") (pinfunction "DAT1/RSV_8") (pintype "passive"))
      (node (ref "R15") (pin "2") (pinfunction "2_2") (pintype "passive"))
    )
    (net (code "64") (name "Net-(NC(P5)-DAT2{slash}RSV)") (class "Default")
      (node (ref "NC(P5)") (pin "1") (pinfunction "DAT2/RSV_1") (pintype "passive"))
      (node (ref "R12") (pin "1") (pinfunction "1_1") (pintype "passive"))
    )
    (net (code "65") (name "Net-(NC(P12)-CC-PadA5)") (class "Default")
      (node (ref "NC(P12)") (pin "A5") (pinfunction "CC_A5") (pintype "bidirectional"))
      (node (ref "R25") (pin "1") (pinfunction "1_1") (pintype "passive"))
    )
    (net (code "66") (name "Net-(NC(P12)-CC-PadB5)") (class "Default")
      (node (ref "NC(P12)") (pin "B5") (pinfunction "CC_B5") (pintype "bidirectional"))
      (node (ref "R24") (pin "1") (pinfunction "1_1") (pintype "passive"))
    )
    (net (code "67") (name "Net-(P3-Pad2)") (class "Default")
      (node (ref "P3") (pin "2") (pinfunction "2_2") (pintype "passive"))
      (node (ref "R6") (pin "1") (pinfunction "1_1") (pintype "passive"))
    )
    (net (code "68") (name "Net-(P_USB-CC-PadA5)") (class "Default")
      (node (ref "P_USB") (pin "A5") (pinfunction "CC_A5") (pintype "bidirectional"))
      (node (ref "R22") (pin "1") (pinfunction "1_1") (pintype "passive"))
    )
    (net (code "69") (name "Net-(P_USB-CC-PadB5)") (class "Default")
      (node (ref "P_USB") (pin "B5") (pinfunction "CC_B5") (pintype "bidirectional"))
      (node (ref "R23") (pin "1") (pinfunction "1_1") (pintype "passive"))
    )
    (net (code "70") (name "Net-(U4-CS#)") (class "Default")
      (node (ref "R10") (pin "1") (pintype "passive"))
      (node (ref "R11") (pin "1") (pinfunction "1_1") (pintype "passive"))
      (node (ref "U4") (pin "1") (pinfunction "CS#_1") (pintype "input"))
    )
    (net (code "71") (name "Net-(U6-RS)") (class "Default")
      (node (ref "R16") (pin "2") (pinfunction "2_2") (pintype "passive"))
      (node (ref "U6") (pin "8") (pinfunction "RS_8") (pintype "passive"))
    )
    (net (code "72") (name "unconnected-(NC(P12)-RFU1-PadA8)") (class "Default")
      (node (ref "NC(P12)") (pin "A8") (pinfunction "RFU1_A8") (pintype "bidirectional+no_connect"))
    )
    (net (code "73") (name "unconnected-(NC(P12)-RFU1-PadB8)") (class "Default")
      (node (ref "NC(P12)") (pin "B8") (pinfunction "RFU1_B8") (pintype "bidirectional+no_connect"))
    )
    (net (code "74") (name "unconnected-(P_USB-RFU1-PadA8)") (class "Default")
      (node (ref "P_USB") (pin "A8") (pinfunction "RFU1_A8") (pintype "bidirectional+no_connect"))
    )
    (net (code "75") (name "unconnected-(P_USB-RFU1-PadB8)") (class "Default")
      (node (ref "P_USB") (pin "B8") (pinfunction "RFU1_B8") (pintype "bidirectional+no_connect"))
    )
    (net (code "76") (name "unconnected-(S2-Pad3)") (class "Default")
      (node (ref "S2") (pin "3") (pinfunction "3_3") (pintype "passive"))
    )
    (net (code "77") (name "unconnected-(U5-CTS#-Pad5)") (class "Default")
      (node (ref "U5") (pin "5") (pinfunction "CTS#_5") (pintype "input+no_connect"))
    )
    (net (code "78") (name "unconnected-(U6-Vref-Pad5)") (class "Default")
      (node (ref "U6") (pin "5") (pinfunction "Vref_5") (pintype "passive"))
    )
  )
)
